# first_schematic.net
KiCad netlist of a schematic drawn in EAGLE
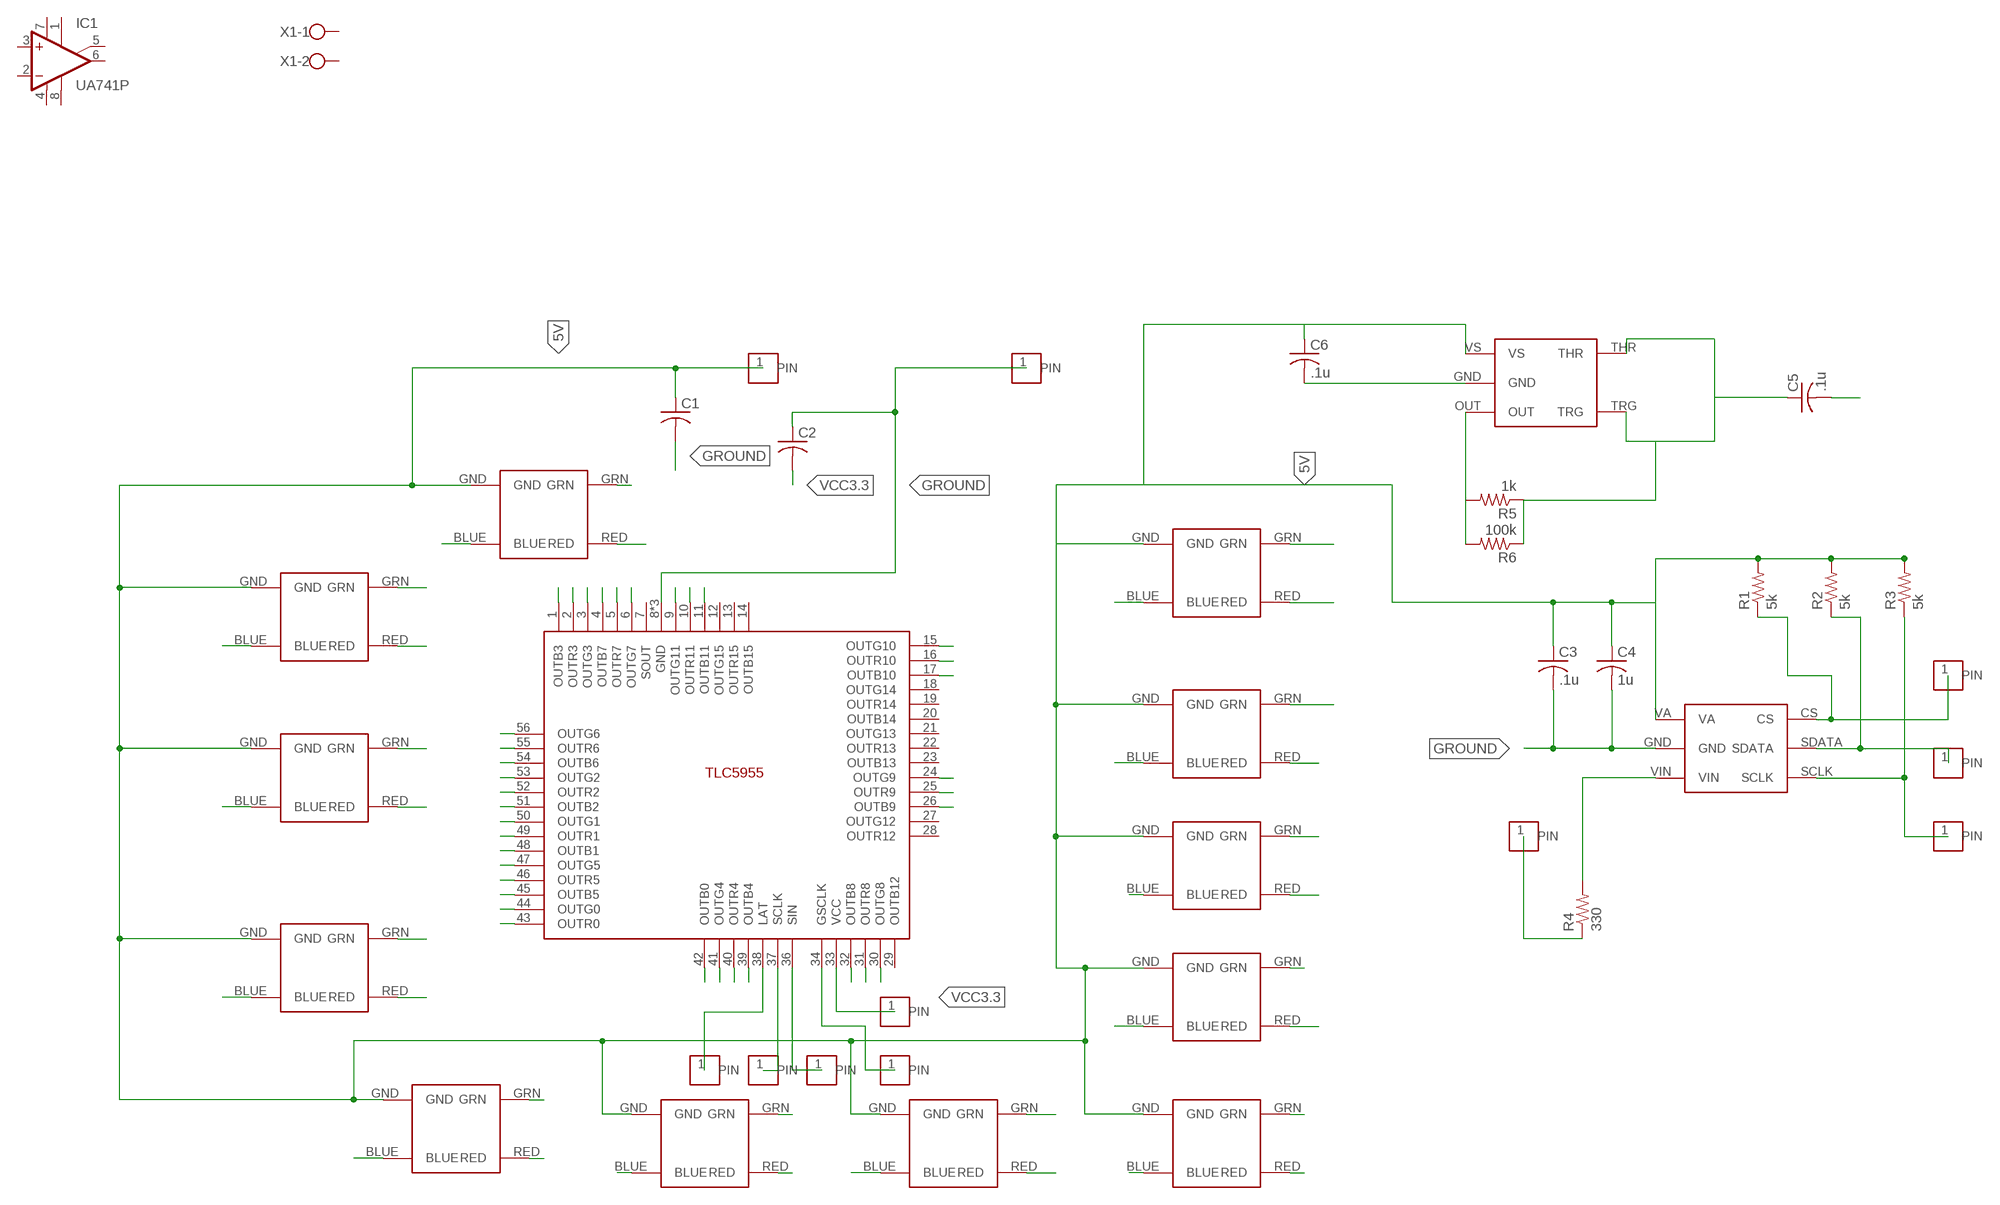
[diagram p0: schematic, sheet 1]

(export (version "E")
  (design (tool "Eeschema 10.0.6"))
  (components
    (comp (ref "3.3V")
      (value "HEADERPIN_1")
      (footprint "eagle-import:HEADERPIN_1")
      (libsource (lib "eagle-import") (part "HEADERPIN_1"))
    )
    (comp (ref "5V")
      (value "HEADERPIN_1")
      (footprint "eagle-import:HEADERPIN_1")
      (libsource (lib "eagle-import") (part "HEADERPIN_1"))
    )
    (comp (ref "C1")
      (value "C-USC0805")
      (footprint "eagle-import:C0805")
      (libsource (lib "eagle-import") (part "C-USC0805"))
    )
    (comp (ref "C2")
      (value "C-USC0805")
      (footprint "eagle-import:C0805")
      (libsource (lib "eagle-import") (part "C-USC0805"))
    )
    (comp (ref "C3")
      (value ".1u")
      (footprint "eagle-import:C0805")
      (libsource (lib "eagle-import") (part "C-USC0805"))
    )
    (comp (ref "C4")
      (value "1u")
      (footprint "eagle-import:C0805")
      (libsource (lib "eagle-import") (part "C-USC0805"))
    )
    (comp (ref "C5")
      (value ".1u")
      (footprint "eagle-import:C0805")
      (libsource (lib "eagle-import") (part "C-USC0805"))
    )
    (comp (ref "C6")
      (value ".1u")
      (footprint "eagle-import:C0805")
      (libsource (lib "eagle-import") (part "C-USC0805"))
    )
    (comp (ref "CS")
      (value "HEADERPIN_1")
      (footprint "eagle-import:HEADERPIN_1")
      (libsource (lib "eagle-import") (part "HEADERPIN_1"))
    )
    (comp (ref "GRND")
      (value "HEADERPIN_1")
      (footprint "eagle-import:HEADERPIN_1")
      (libsource (lib "eagle-import") (part "HEADERPIN_1"))
    )
    (comp (ref "GSCLK")
      (value "HEADERPIN_1")
      (footprint "eagle-import:HEADERPIN_1")
      (libsource (lib "eagle-import") (part "HEADERPIN_1"))
    )
    (comp (ref "IC1")
      (value "UA741P")
      (footprint "eagle-import:DIL08")
      (libsource (lib "eagle-import") (part "741PUA"))
    )
    (comp (ref "LAT")
      (value "HEADERPIN_1")
      (footprint "eagle-import:HEADERPIN_1")
      (libsource (lib "eagle-import") (part "HEADERPIN_1"))
    )
    (comp (ref "R1")
      (value "5k")
      (footprint "eagle-import:M0805")
      (libsource (lib "eagle-import") (part "R-US_M0805"))
    )
    (comp (ref "R2")
      (value "5k")
      (footprint "eagle-import:M0805")
      (libsource (lib "eagle-import") (part "R-US_M0805"))
    )
    (comp (ref "R3")
      (value "5k")
      (footprint "eagle-import:M0805")
      (libsource (lib "eagle-import") (part "R-US_M0805"))
    )
    (comp (ref "R4")
      (value "330")
      (footprint "eagle-import:M0805")
      (libsource (lib "eagle-import") (part "R-US_M0805"))
    )
    (comp (ref "R5")
      (value "1k")
      (footprint "eagle-import:M0805")
      (libsource (lib "eagle-import") (part "R-US_M0805"))
    )
    (comp (ref "R6")
      (value "100k")
      (footprint "eagle-import:M0805")
      (libsource (lib "eagle-import") (part "R-US_M0805"))
    )
    (comp (ref "SCLK")
      (value "HEADERPIN_1")
      (footprint "eagle-import:HEADERPIN_1")
      (libsource (lib "eagle-import") (part "HEADERPIN_1"))
    )
    (comp (ref "SIN")
      (value "HEADERPIN_1")
      (footprint "eagle-import:HEADERPIN_1")
      (libsource (lib "eagle-import") (part "HEADERPIN_1"))
    )
    (comp (ref "SLK")
      (value "HEADERPIN_1")
      (footprint "eagle-import:HEADERPIN_1")
      (libsource (lib "eagle-import") (part "HEADERPIN_1"))
    )
    (comp (ref "TLC5955")
      (value "TLC5954")
      (footprint "eagle-import:TLC5955")
      (libsource (lib "eagle-import") (part "TLC5954"))
    )
    (comp (ref "TRG2")
      (value "HEADERPIN_1")
      (footprint "eagle-import:HEADERPIN_1")
      (libsource (lib "eagle-import") (part "HEADERPIN_1"))
    )
    (comp (ref "U$1")
      (value "MIC1555")
      (footprint "eagle-import:SOT-23")
      (libsource (lib "eagle-import") (part "MIC1555"))
    )
    (comp (ref "U$2")
      (value "KINGSBRIGHT_LED_3.5X2.8")
      (footprint "eagle-import:KINGSBRIGHT_LED_3.5X2.8")
      (libsource (lib "eagle-import") (part "KINGSBRIGHT_LED_3.5X2.8"))
    )
    (comp (ref "U$3")
      (value "KINGSBRIGHT_LED_3.5X2.8")
      (footprint "eagle-import:KINGSBRIGHT_LED_3.5X2.8")
      (libsource (lib "eagle-import") (part "KINGSBRIGHT_LED_3.5X2.8"))
    )
    (comp (ref "U$4")
      (value "KINGSBRIGHT_LED_3.5X2.8")
      (footprint "eagle-import:KINGSBRIGHT_LED_3.5X2.8")
      (libsource (lib "eagle-import") (part "KINGSBRIGHT_LED_3.5X2.8"))
    )
    (comp (ref "U$5")
      (value "KINGSBRIGHT_LED_3.5X2.8")
      (footprint "eagle-import:KINGSBRIGHT_LED_3.5X2.8")
      (libsource (lib "eagle-import") (part "KINGSBRIGHT_LED_3.5X2.8"))
    )
    (comp (ref "U$6")
      (value "KINGSBRIGHT_LED_3.5X2.8")
      (footprint "eagle-import:KINGSBRIGHT_LED_3.5X2.8")
      (libsource (lib "eagle-import") (part "KINGSBRIGHT_LED_3.5X2.8"))
    )
    (comp (ref "U$7")
      (value "KINGSBRIGHT_LED_3.5X2.8")
      (footprint "eagle-import:KINGSBRIGHT_LED_3.5X2.8")
      (libsource (lib "eagle-import") (part "KINGSBRIGHT_LED_3.5X2.8"))
    )
    (comp (ref "U$8")
      (value "KINGSBRIGHT_LED_3.5X2.8")
      (footprint "eagle-import:KINGSBRIGHT_LED_3.5X2.8")
      (libsource (lib "eagle-import") (part "KINGSBRIGHT_LED_3.5X2.8"))
    )
    (comp (ref "U$9")
      (value "KINGSBRIGHT_LED_3.5X2.8")
      (footprint "eagle-import:KINGSBRIGHT_LED_3.5X2.8")
      (libsource (lib "eagle-import") (part "KINGSBRIGHT_LED_3.5X2.8"))
    )
    (comp (ref "U$10")
      (value "KINGSBRIGHT_LED_3.5X2.8")
      (footprint "eagle-import:KINGSBRIGHT_LED_3.5X2.8")
      (libsource (lib "eagle-import") (part "KINGSBRIGHT_LED_3.5X2.8"))
    )
    (comp (ref "U$11")
      (value "KINGSBRIGHT_LED_3.5X2.8")
      (footprint "eagle-import:KINGSBRIGHT_LED_3.5X2.8")
      (libsource (lib "eagle-import") (part "KINGSBRIGHT_LED_3.5X2.8"))
    )
    (comp (ref "U$12")
      (value "KINGSBRIGHT_LED_3.5X2.8")
      (footprint "eagle-import:KINGSBRIGHT_LED_3.5X2.8")
      (libsource (lib "eagle-import") (part "KINGSBRIGHT_LED_3.5X2.8"))
    )
    (comp (ref "U$13")
      (value "KINGSBRIGHT_LED_3.5X2.8")
      (footprint "eagle-import:KINGSBRIGHT_LED_3.5X2.8")
      (libsource (lib "eagle-import") (part "KINGSBRIGHT_LED_3.5X2.8"))
    )
    (comp (ref "U$14")
      (value "ADC121S101")
      (footprint "eagle-import:SOT-23(6)")
      (libsource (lib "eagle-import") (part "ADC121S101"))
    )
    (comp (ref "VIN")
      (value "HEADERPIN_1")
      (footprint "eagle-import:HEADERPIN_1")
      (libsource (lib "eagle-import") (part "HEADERPIN_1"))
    )
    (comp (ref "X1")
      (value "W237-102")
      (footprint "eagle-import:W237-102")
      (fields (field (name "MPN") "237-102"))
      (libsource (lib "eagle-import") (part "W237-102"))
    )
  )
  (nets
    (net (code "1") (name "/B0") (class "Default")
      (node (ref "TLC5955") (pin "42") (pinfunction "OUTB0_42") (pintype "bidirectional"))
      (node (ref "U$13") (pin "BLUE") (pinfunction "BLUE_BLUE") (pintype "bidirectional"))
    )
    (net (code "2") (name "/B1") (class "Default")
      (node (ref "TLC5955") (pin "48") (pinfunction "OUTB1_48") (pintype "bidirectional"))
      (node (ref "U$12") (pin "BLUE") (pinfunction "BLUE_BLUE") (pintype "bidirectional"))
    )
    (net (code "3") (name "/B2") (class "Default")
      (node (ref "TLC5955") (pin "51") (pinfunction "OUTB2_51") (pintype "bidirectional"))
      (node (ref "U$11") (pin "BLUE") (pinfunction "BLUE_BLUE") (pintype "bidirectional"))
    )
    (net (code "4") (name "/B3") (class "Default")
      (node (ref "TLC5955") (pin "1") (pinfunction "OUTB3_1") (pintype "bidirectional"))
      (node (ref "U$10") (pin "BLUE") (pinfunction "BLUE_BLUE") (pintype "bidirectional"))
    )
    (net (code "5") (name "/B4") (class "Default")
      (node (ref "TLC5955") (pin "39") (pinfunction "OUTB4_39") (pintype "bidirectional"))
      (node (ref "U$9") (pin "BLUE") (pinfunction "BLUE_BLUE") (pintype "bidirectional"))
    )
    (net (code "6") (name "/B5") (class "Default")
      (node (ref "TLC5955") (pin "45") (pinfunction "OUTB5_45") (pintype "bidirectional"))
      (node (ref "U$8") (pin "BLUE") (pinfunction "BLUE_BLUE") (pintype "bidirectional"))
    )
    (net (code "7") (name "/B6") (class "Default")
      (node (ref "TLC5955") (pin "54") (pinfunction "OUTB6_54") (pintype "bidirectional"))
      (node (ref "U$7") (pin "BLUE") (pinfunction "BLUE_BLUE") (pintype "bidirectional"))
    )
    (net (code "8") (name "/B7") (class "Default")
      (node (ref "TLC5955") (pin "4") (pinfunction "OUTB7_4") (pintype "bidirectional"))
      (node (ref "U$6") (pin "BLUE") (pinfunction "BLUE_BLUE") (pintype "bidirectional"))
    )
    (net (code "9") (name "/B8") (class "Default")
      (node (ref "TLC5955") (pin "32") (pinfunction "OUTB8_32") (pintype "bidirectional"))
      (node (ref "U$5") (pin "BLUE") (pinfunction "BLUE_BLUE") (pintype "bidirectional"))
    )
    (net (code "10") (name "/B9") (class "Default")
      (node (ref "TLC5955") (pin "26") (pinfunction "OUTB9_26") (pintype "bidirectional"))
      (node (ref "U$4") (pin "BLUE") (pinfunction "BLUE_BLUE") (pintype "bidirectional"))
    )
    (net (code "11") (name "/B10") (class "Default")
      (node (ref "TLC5955") (pin "17") (pinfunction "OUTB10_17") (pintype "bidirectional"))
      (node (ref "U$3") (pin "BLUE") (pinfunction "BLUE_BLUE") (pintype "bidirectional"))
    )
    (net (code "12") (name "/B11") (class "Default")
      (node (ref "TLC5955") (pin "11") (pinfunction "OUTB11_11") (pintype "bidirectional"))
      (node (ref "U$2") (pin "BLUE") (pinfunction "BLUE_BLUE") (pintype "bidirectional"))
    )
    (net (code "13") (name "/G0") (class "Default")
      (node (ref "TLC5955") (pin "44") (pinfunction "OUTG0_44") (pintype "bidirectional"))
      (node (ref "U$13") (pin "GRN") (pinfunction "GRN_GRN") (pintype "bidirectional"))
    )
    (net (code "14") (name "/G1") (class "Default")
      (node (ref "TLC5955") (pin "50") (pinfunction "OUTG1_50") (pintype "bidirectional"))
      (node (ref "U$12") (pin "GRN") (pinfunction "GRN_GRN") (pintype "bidirectional"))
    )
    (net (code "15") (name "/G2") (class "Default")
      (node (ref "TLC5955") (pin "53") (pinfunction "OUTG2_53") (pintype "bidirectional"))
      (node (ref "U$11") (pin "GRN") (pinfunction "GRN_GRN") (pintype "bidirectional"))
    )
    (net (code "16") (name "/G3") (class "Default")
      (node (ref "TLC5955") (pin "3") (pinfunction "OUTG3_3") (pintype "bidirectional"))
      (node (ref "U$10") (pin "GRN") (pinfunction "GRN_GRN") (pintype "bidirectional"))
    )
    (net (code "17") (name "/G4") (class "Default")
      (node (ref "TLC5955") (pin "41") (pinfunction "OUTG4_41") (pintype "bidirectional"))
      (node (ref "U$9") (pin "GRN") (pinfunction "GRN_GRN") (pintype "bidirectional"))
    )
    (net (code "18") (name "/G5") (class "Default")
      (node (ref "TLC5955") (pin "47") (pinfunction "OUTG5_47") (pintype "bidirectional"))
      (node (ref "U$8") (pin "GRN") (pinfunction "GRN_GRN") (pintype "bidirectional"))
    )
    (net (code "19") (name "/G6") (class "Default")
      (node (ref "TLC5955") (pin "56") (pinfunction "OUTG6_56") (pintype "bidirectional"))
      (node (ref "U$7") (pin "GRN") (pinfunction "GRN_GRN") (pintype "bidirectional"))
    )
    (net (code "20") (name "/G7") (class "Default")
      (node (ref "TLC5955") (pin "6") (pinfunction "OUTG7_6") (pintype "bidirectional"))
      (node (ref "U$6") (pin "GRN") (pinfunction "GRN_GRN") (pintype "bidirectional"))
    )
    (net (code "21") (name "/G8") (class "Default")
      (node (ref "TLC5955") (pin "30") (pinfunction "OUTG8_30") (pintype "bidirectional"))
      (node (ref "U$5") (pin "GRN") (pinfunction "GRN_GRN") (pintype "bidirectional"))
    )
    (net (code "22") (name "/G9") (class "Default")
      (node (ref "TLC5955") (pin "24") (pinfunction "OUTG9_24") (pintype "bidirectional"))
      (node (ref "U$4") (pin "GRN") (pinfunction "GRN_GRN") (pintype "bidirectional"))
    )
    (net (code "23") (name "/G10") (class "Default")
      (node (ref "TLC5955") (pin "15") (pinfunction "OUTG10_15") (pintype "bidirectional"))
      (node (ref "U$3") (pin "GRN") (pinfunction "GRN_GRN") (pintype "bidirectional"))
    )
    (net (code "24") (name "/G11") (class "Default")
      (node (ref "TLC5955") (pin "9") (pinfunction "OUTG11_9") (pintype "bidirectional"))
      (node (ref "U$2") (pin "GRN") (pinfunction "GRN_GRN") (pintype "bidirectional"))
    )
    (net (code "25") (name "/GSCLK") (class "Default")
      (node (ref "GSCLK") (pin "1") (pinfunction "PIN_1") (pintype "bidirectional"))
      (node (ref "R5") (pin "2") (pinfunction "2_2") (pintype "passive"))
      (node (ref "R6") (pin "2") (pinfunction "2_2") (pintype "passive"))
      (node (ref "TLC5955") (pin "34") (pinfunction "GSCLK_34") (pintype "bidirectional"))
      (node (ref "U$1") (pin "OUT") (pinfunction "OUT_OUT") (pintype "bidirectional"))
    )
    (net (code "26") (name "/R0") (class "Default")
      (node (ref "TLC5955") (pin "43") (pinfunction "OUTR0_43") (pintype "bidirectional"))
      (node (ref "U$13") (pin "RED") (pinfunction "RED_RED") (pintype "bidirectional"))
    )
    (net (code "27") (name "/R1") (class "Default")
      (node (ref "TLC5955") (pin "49") (pinfunction "OUTR1_49") (pintype "bidirectional"))
      (node (ref "U$12") (pin "RED") (pinfunction "RED_RED") (pintype "bidirectional"))
    )
    (net (code "28") (name "/R2") (class "Default")
      (node (ref "TLC5955") (pin "52") (pinfunction "OUTR2_52") (pintype "bidirectional"))
      (node (ref "U$11") (pin "RED") (pinfunction "RED_RED") (pintype "bidirectional"))
    )
    (net (code "29") (name "/R3") (class "Default")
      (node (ref "TLC5955") (pin "2") (pinfunction "OUTR3_2") (pintype "bidirectional"))
      (node (ref "U$10") (pin "RED") (pinfunction "RED_RED") (pintype "bidirectional"))
    )
    (net (code "30") (name "/R4") (class "Default")
      (node (ref "TLC5955") (pin "40") (pinfunction "OUTR4_40") (pintype "bidirectional"))
      (node (ref "U$9") (pin "RED") (pinfunction "RED_RED") (pintype "bidirectional"))
    )
    (net (code "31") (name "/R5") (class "Default")
      (node (ref "TLC5955") (pin "46") (pinfunction "OUTR5_46") (pintype "bidirectional"))
      (node (ref "U$8") (pin "RED") (pinfunction "RED_RED") (pintype "bidirectional"))
    )
    (net (code "32") (name "/R6") (class "Default")
      (node (ref "TLC5955") (pin "55") (pinfunction "OUTR6_55") (pintype "bidirectional"))
      (node (ref "U$7") (pin "RED") (pinfunction "RED_RED") (pintype "bidirectional"))
    )
    (net (code "33") (name "/R7") (class "Default")
      (node (ref "TLC5955") (pin "5") (pinfunction "OUTR7_5") (pintype "bidirectional"))
      (node (ref "U$6") (pin "RED") (pinfunction "RED_RED") (pintype "bidirectional"))
    )
    (net (code "34") (name "/R8") (class "Default")
      (node (ref "TLC5955") (pin "31") (pinfunction "OUTR8_31") (pintype "bidirectional"))
      (node (ref "U$5") (pin "RED") (pinfunction "RED_RED") (pintype "bidirectional"))
    )
    (net (code "35") (name "/R9") (class "Default")
      (node (ref "TLC5955") (pin "25") (pinfunction "OUTR9_25") (pintype "bidirectional"))
      (node (ref "U$4") (pin "RED") (pinfunction "RED_RED") (pintype "bidirectional"))
    )
    (net (code "36") (name "/R10") (class "Default")
      (node (ref "TLC5955") (pin "16") (pinfunction "OUTR10_16") (pintype "bidirectional"))
      (node (ref "U$3") (pin "RED") (pinfunction "RED_RED") (pintype "bidirectional"))
    )
    (net (code "37") (name "/R11") (class "Default")
      (node (ref "TLC5955") (pin "10") (pinfunction "OUTR11_10") (pintype "bidirectional"))
      (node (ref "U$2") (pin "RED") (pinfunction "RED_RED") (pintype "bidirectional"))
    )
    (net (code "38") (name "/V+") (class "Default")
      (node (ref "IC1") (pin "7") (pinfunction "V+_7") (pintype "power_in"))
    )
    (net (code "39") (name "/V-") (class "Default")
      (node (ref "IC1") (pin "4") (pinfunction "V-_4") (pintype "power_in"))
    )
    (net (code "40") (name "5V") (class "Default")
      (node (ref "5V") (pin "1") (pinfunction "PIN_1") (pintype "bidirectional"))
      (node (ref "C1") (pin "1") (pinfunction "1_1") (pintype "passive"))
      (node (ref "C3") (pin "1") (pinfunction "1_1") (pintype "passive"))
      (node (ref "C4") (pin "1") (pinfunction "1_1") (pintype "passive"))
      (node (ref "C6") (pin "1") (pinfunction "1_1") (pintype "passive"))
      (node (ref "R1") (pin "2") (pinfunction "2_2") (pintype "passive"))
      (node (ref "R2") (pin "2") (pinfunction "2_2") (pintype "passive"))
      (node (ref "R3") (pin "2") (pinfunction "2_2") (pintype "passive"))
      (node (ref "U$1") (pin "VS") (pinfunction "VS_VS") (pintype "bidirectional"))
      (node (ref "U$10") (pin "GND") (pinfunction "GND_GND") (pintype "bidirectional"))
      (node (ref "U$11") (pin "GND") (pinfunction "GND_GND") (pintype "bidirectional"))
      (node (ref "U$12") (pin "GND") (pinfunction "GND_GND") (pintype "bidirectional"))
      (node (ref "U$13") (pin "GND") (pinfunction "GND_GND") (pintype "bidirectional"))
      (node (ref "U$14") (pin "VA") (pinfunction "VA_VA") (pintype "bidirectional"))
      (node (ref "U$2") (pin "GND") (pinfunction "GND_GND") (pintype "bidirectional"))
      (node (ref "U$3") (pin "GND") (pinfunction "GND_GND") (pintype "bidirectional"))
      (node (ref "U$4") (pin "GND") (pinfunction "GND_GND") (pintype "bidirectional"))
      (node (ref "U$5") (pin "GND") (pinfunction "GND_GND") (pintype "bidirectional"))
      (node (ref "U$6") (pin "GND") (pinfunction "GND_GND") (pintype "bidirectional"))
      (node (ref "U$7") (pin "GND") (pinfunction "GND_GND") (pintype "bidirectional"))
      (node (ref "U$8") (pin "GND") (pinfunction "GND_GND") (pintype "bidirectional"))
      (node (ref "U$9") (pin "GND") (pinfunction "GND_GND") (pintype "bidirectional"))
    )
    (net (code "41") (name "GROUND") (class "Default")
      (node (ref "C1") (pin "2") (pinfunction "2_2") (pintype "passive"))
      (node (ref "C2") (pin "1") (pinfunction "1_1") (pintype "passive"))
      (node (ref "C3") (pin "2") (pinfunction "2_2") (pintype "passive"))
      (node (ref "C4") (pin "2") (pinfunction "2_2") (pintype "passive"))
      (node (ref "C5") (pin "2") (pinfunction "2_2") (pintype "passive"))
      (node (ref "C6") (pin "2") (pinfunction "2_2") (pintype "passive"))
      (node (ref "GRND") (pin "1") (pinfunction "PIN_1") (pintype "bidirectional"))
      (node (ref "TLC5955") (pin "35") (pinfunction "GND_35") (pintype "bidirectional"))
      (node (ref "TLC5955") (pin "8") (pinfunction "GND_8") (pintype "bidirectional"))
      (node (ref "TLC5955") (pin "HEATSINK") (pinfunction "GND_HEATSINK") (pintype "bidirectional"))
      (node (ref "U$1") (pin "GND") (pinfunction "GND_GND") (pintype "bidirectional"))
      (node (ref "U$14") (pin "GND") (pinfunction "GND_GND") (pintype "bidirectional"))
    )
    (net (code "42") (name "Net-(C5-Pad1)") (class "Default")
      (node (ref "C5") (pin "1") (pinfunction "1_1") (pintype "passive"))
      (node (ref "R5") (pin "1") (pinfunction "1_1") (pintype "passive"))
      (node (ref "R6") (pin "1") (pinfunction "1_1") (pintype "passive"))
      (node (ref "U$1") (pin "THR") (pinfunction "THR_THR") (pintype "bidirectional"))
      (node (ref "U$1") (pin "TRG") (pinfunction "TRG_TRG") (pintype "bidirectional"))
    )
    (net (code "43") (name "Net-(CS-PIN)") (class "Default")
      (node (ref "CS") (pin "1") (pinfunction "PIN_1") (pintype "bidirectional"))
      (node (ref "R1") (pin "1") (pinfunction "1_1") (pintype "passive"))
      (node (ref "U$14") (pin "CS") (pinfunction "CS_CS") (pintype "bidirectional"))
    )
    (net (code "44") (name "Net-(LAT-PIN)") (class "Default")
      (node (ref "LAT") (pin "1") (pinfunction "PIN_1") (pintype "bidirectional"))
      (node (ref "TLC5955") (pin "38") (pinfunction "LAT_38") (pintype "bidirectional"))
    )
    (net (code "45") (name "Net-(R4-Pad2)") (class "Default")
      (node (ref "R4") (pin "2") (pinfunction "2_2") (pintype "passive"))
      (node (ref "U$14") (pin "VIN") (pinfunction "VIN_VIN") (pintype "bidirectional"))
    )
    (net (code "46") (name "Net-(SCLK-PIN)") (class "Default")
      (node (ref "SCLK") (pin "1") (pinfunction "PIN_1") (pintype "bidirectional"))
      (node (ref "TLC5955") (pin "37") (pinfunction "SCLK_37") (pintype "bidirectional"))
    )
    (net (code "47") (name "Net-(SIN-PIN)") (class "Default")
      (node (ref "SIN") (pin "1") (pinfunction "PIN_1") (pintype "bidirectional"))
      (node (ref "TLC5955") (pin "36") (pinfunction "SIN_36") (pintype "bidirectional"))
    )
    (net (code "48") (name "Net-(SLK-PIN)") (class "Default")
      (node (ref "R3") (pin "1") (pinfunction "1_1") (pintype "passive"))
      (node (ref "SLK") (pin "1") (pinfunction "PIN_1") (pintype "bidirectional"))
      (node (ref "U$14") (pin "SCLK") (pinfunction "SCLK_SCLK") (pintype "bidirectional"))
    )
    (net (code "49") (name "Net-(TRG2-PIN)") (class "Default")
      (node (ref "R2") (pin "1") (pinfunction "1_1") (pintype "passive"))
      (node (ref "TRG2") (pin "1") (pinfunction "PIN_1") (pintype "bidirectional"))
      (node (ref "U$14") (pin "SDATA") (pinfunction "SDATA_SDATA") (pintype "bidirectional"))
    )
    (net (code "50") (name "Net-(VIN-PIN)") (class "Default")
      (node (ref "R4") (pin "1") (pinfunction "1_1") (pintype "passive"))
      (node (ref "VIN") (pin "1") (pinfunction "PIN_1") (pintype "bidirectional"))
    )
    (net (code "51") (name "VCC3.3") (class "Default")
      (node (ref "3.3V") (pin "1") (pinfunction "PIN_1") (pintype "bidirectional"))
      (node (ref "C2") (pin "2") (pinfunction "2_2") (pintype "passive"))
      (node (ref "TLC5955") (pin "33") (pinfunction "VCC_33") (pintype "bidirectional"))
    )
    (net (code "52") (name "unconnected-(IC1-+IN-Pad3)") (class "Default")
      (node (ref "IC1") (pin "3") (pinfunction "+IN_3") (pintype "input"))
    )
    (net (code "53") (name "unconnected-(IC1--IN-Pad2)") (class "Default")
      (node (ref "IC1") (pin "2") (pinfunction "-IN_2") (pintype "input"))
    )
    (net (code "54") (name "unconnected-(IC1-ON1-Pad1)") (class "Default")
      (node (ref "IC1") (pin "1") (pinfunction "ON1_1") (pintype "passive"))
    )
    (net (code "55") (name "unconnected-(IC1-ON2-Pad5)") (class "Default")
      (node (ref "IC1") (pin "5") (pinfunction "ON2_5") (pintype "passive"))
    )
    (net (code "56") (name "unconnected-(IC1-OPT-Pad8)") (class "Default")
      (node (ref "IC1") (pin "8") (pinfunction "OPT_8") (pintype "passive"))
    )
    (net (code "57") (name "unconnected-(IC1-OUT-Pad6)") (class "Default")
      (node (ref "IC1") (pin "6") (pinfunction "OUT_6") (pintype "output"))
    )
    (net (code "58") (name "unconnected-(TLC5955-OUTB12-Pad29)") (class "Default")
      (node (ref "TLC5955") (pin "29") (pinfunction "OUTB12_29") (pintype "bidirectional"))
    )
    (net (code "59") (name "unconnected-(TLC5955-OUTB13-Pad23)") (class "Default")
      (node (ref "TLC5955") (pin "23") (pinfunction "OUTB13_23") (pintype "bidirectional"))
    )
    (net (code "60") (name "unconnected-(TLC5955-OUTB14-Pad20)") (class "Default")
      (node (ref "TLC5955") (pin "20") (pinfunction "OUTB14_20") (pintype "bidirectional"))
    )
    (net (code "61") (name "unconnected-(TLC5955-OUTB15-Pad14)") (class "Default")
      (node (ref "TLC5955") (pin "14") (pinfunction "OUTB15_14") (pintype "bidirectional"))
    )
    (net (code "62") (name "unconnected-(TLC5955-OUTG12-Pad27)") (class "Default")
      (node (ref "TLC5955") (pin "27") (pinfunction "OUTG12_27") (pintype "bidirectional"))
    )
    (net (code "63") (name "unconnected-(TLC5955-OUTG13-Pad21)") (class "Default")
      (node (ref "TLC5955") (pin "21") (pinfunction "OUTG13_21") (pintype "bidirectional"))
    )
    (net (code "64") (name "unconnected-(TLC5955-OUTG14-Pad18)") (class "Default")
      (node (ref "TLC5955") (pin "18") (pinfunction "OUTG14_18") (pintype "bidirectional"))
    )
    (net (code "65") (name "unconnected-(TLC5955-OUTG15-Pad12)") (class "Default")
      (node (ref "TLC5955") (pin "12") (pinfunction "OUTG15_12") (pintype "bidirectional"))
    )
    (net (code "66") (name "unconnected-(TLC5955-OUTR12-Pad28)") (class "Default")
      (node (ref "TLC5955") (pin "28") (pinfunction "OUTR12_28") (pintype "bidirectional"))
    )
    (net (code "67") (name "unconnected-(TLC5955-OUTR13-Pad22)") (class "Default")
      (node (ref "TLC5955") (pin "22") (pinfunction "OUTR13_22") (pintype "bidirectional"))
    )
    (net (code "68") (name "unconnected-(TLC5955-OUTR14-Pad19)") (class "Default")
      (node (ref "TLC5955") (pin "19") (pinfunction "OUTR14_19") (pintype "bidirectional"))
    )
    (net (code "69") (name "unconnected-(TLC5955-OUTR15-Pad13)") (class "Default")
      (node (ref "TLC5955") (pin "13") (pinfunction "OUTR15_13") (pintype "bidirectional"))
    )
    (net (code "70") (name "unconnected-(TLC5955-SOUT-Pad7)") (class "Default")
      (node (ref "TLC5955") (pin "7") (pinfunction "SOUT_7") (pintype "bidirectional"))
    )
    (net (code "71") (name "unconnected-(X1A-KL-Pad1)") (class "Default")
      (node (ref "X1") (pin "1") (pinfunction "KL_1") (pintype "passive"))
    )
    (net (code "72") (name "unconnected-(X1B-KL-Pad2)") (class "Default")
      (node (ref "X1") (pin "2") (pinfunction "KL_2") (pintype "passive"))
    )
  )
)
